# domus-silicea-board01-schematic.net
KiCad netlist of a schematic drawn in EAGLE
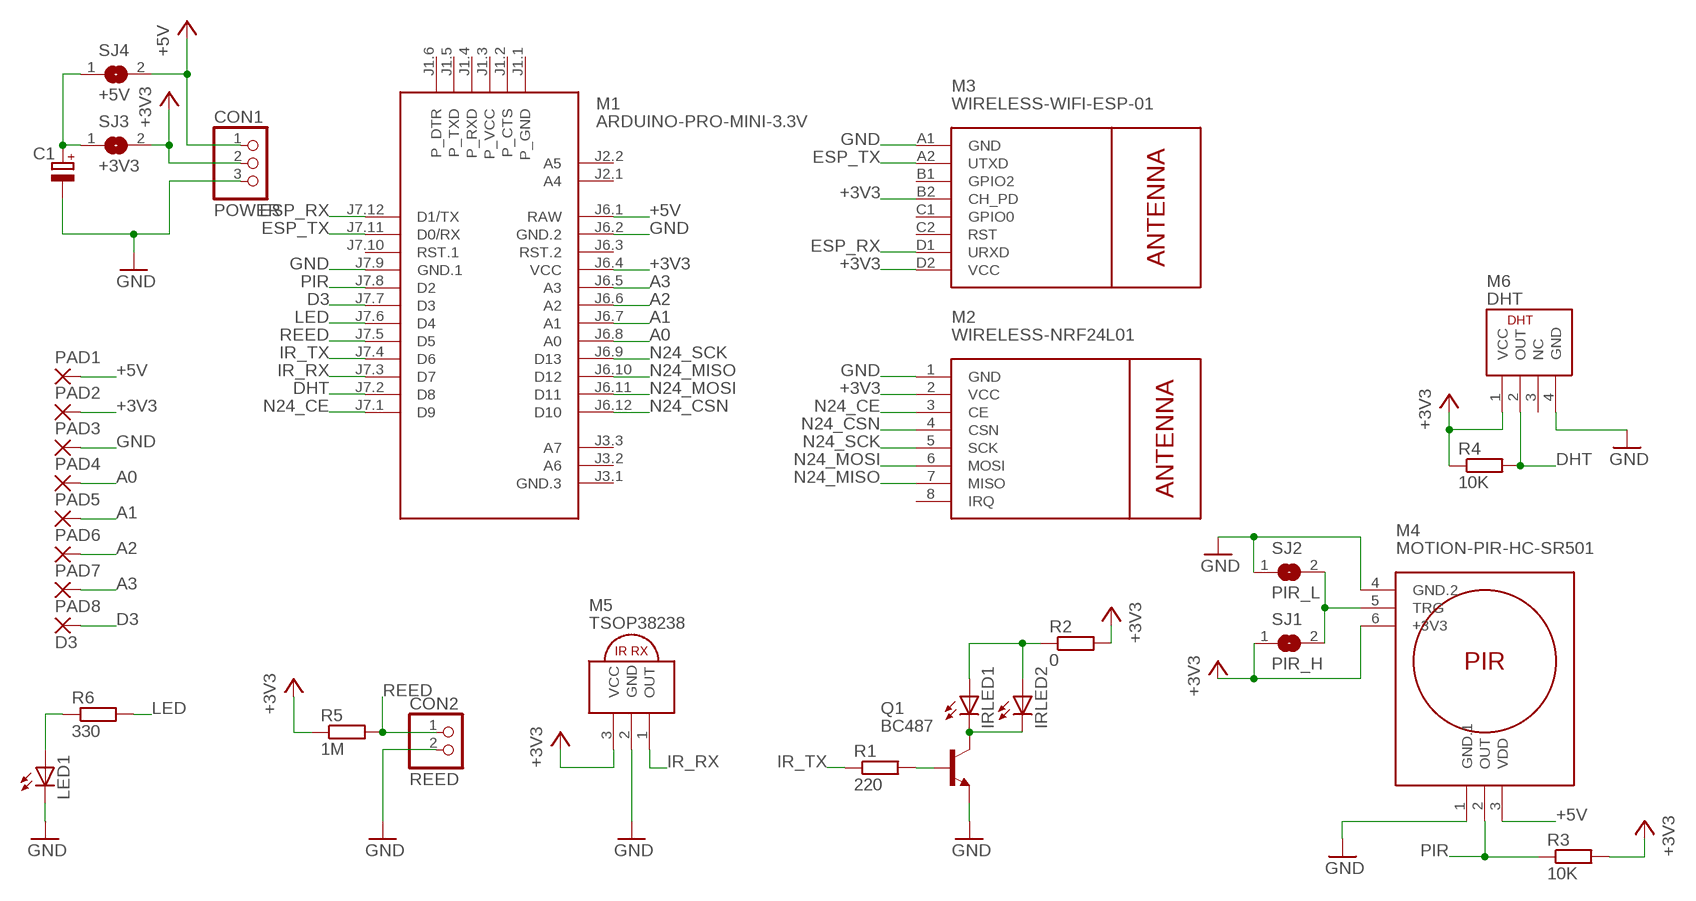
[diagram p0: schematic, sheet 1]

(export (version "E")
  (design (tool "Eeschema 10.0.6"))
  (components
    (comp (ref "C1")
      (value "CPOL-EUE2,5-6E")
      (footprint "eagle-import:E2,5-6E")
      (libsource (lib "eagle-import") (part "CPOL-EUE2,5-6E"))
    )
    (comp (ref "CON1")
      (value "POWER")
      (footprint "eagle-import:1X03")
      (libsource (lib "eagle-import") (part "PINHD-1X3"))
    )
    (comp (ref "CON2")
      (value "REED")
      (footprint "eagle-import:1X02")
      (libsource (lib "eagle-import") (part "PINHD-1X2"))
    )
    (comp (ref "IRLED1")
      (value "LED5MM")
      (footprint "eagle-import:LED5MM")
      (libsource (lib "eagle-import") (part "LED5MM"))
    )
    (comp (ref "IRLED2")
      (value "LED5MM")
      (footprint "eagle-import:LED5MM")
      (libsource (lib "eagle-import") (part "LED5MM"))
    )
    (comp (ref "LED1")
      (value "LED5MM")
      (footprint "eagle-import:LED5MM")
      (libsource (lib "eagle-import") (part "LED5MM"))
    )
    (comp (ref "M1")
      (value "ARDUINO-PRO-MINI-3.3V")
      (footprint "eagle-import:ARDUINO-PRO-MINI")
      (libsource (lib "eagle-import") (part "ARDUINO-PRO-MINI-3.3V"))
    )
    (comp (ref "M2")
      (value "WIRELESS-NRF24L01")
      (footprint "eagle-import:WIRELESS-NRF24L01")
      (libsource (lib "eagle-import") (part "WIRELESS-NRF24L01"))
    )
    (comp (ref "M3")
      (value "WIRELESS-WIFI-ESP-01")
      (footprint "eagle-import:WIRELESS-WIFI-ESP-01")
      (libsource (lib "eagle-import") (part "WIRELESS-WIFI-ESP-01"))
    )
    (comp (ref "M4")
      (value "MOTION-PIR-HC-SR501")
      (footprint "eagle-import:MOTION-PIR-HC-SR501")
      (libsource (lib "eagle-import") (part "MOTION-PIR-HC-SR501"))
    )
    (comp (ref "M5")
      (value "TSOP38238")
      (footprint "eagle-import:TSOP38238")
      (libsource (lib "eagle-import") (part "TSOP38238"))
    )
    (comp (ref "M6")
      (value "DHT")
      (footprint "eagle-import:DHT")
      (libsource (lib "eagle-import") (part "DHT"))
    )
    (comp (ref "PAD1")
      (value "2,54/1,0")
      (footprint "eagle-import:2,54_1,0")
      (libsource (lib "eagle-import") (part "2,54/1,0"))
    )
    (comp (ref "PAD2")
      (value "2,54/1,0")
      (footprint "eagle-import:2,54_1,0")
      (libsource (lib "eagle-import") (part "2,54/1,0"))
    )
    (comp (ref "PAD3")
      (value "2,54/1,0")
      (footprint "eagle-import:2,54_1,0")
      (libsource (lib "eagle-import") (part "2,54/1,0"))
    )
    (comp (ref "PAD4")
      (value "2,54/1,0")
      (footprint "eagle-import:2,54_1,0")
      (libsource (lib "eagle-import") (part "2,54/1,0"))
    )
    (comp (ref "PAD5")
      (value "2,54/1,0")
      (footprint "eagle-import:2,54_1,0")
      (libsource (lib "eagle-import") (part "2,54/1,0"))
    )
    (comp (ref "PAD6")
      (value "2,54/1,0")
      (footprint "eagle-import:2,54_1,0")
      (libsource (lib "eagle-import") (part "2,54/1,0"))
    )
    (comp (ref "PAD7")
      (value "2,54/1,0")
      (footprint "eagle-import:2,54_1,0")
      (libsource (lib "eagle-import") (part "2,54/1,0"))
    )
    (comp (ref "PAD8")
      (value "D3")
      (footprint "eagle-import:2,54_1,0")
      (libsource (lib "eagle-import") (part "2,54/1,0"))
    )
    (comp (ref "Q1")
      (value "BC487")
      (footprint "eagle-import:TO92-EBC")
      (libsource (lib "eagle-import") (part "BC487"))
    )
    (comp (ref "R1")
      (value "220")
      (footprint "eagle-import:0207_10")
      (libsource (lib "eagle-import") (part "R-EU_0207/10"))
    )
    (comp (ref "R2")
      (value "0")
      (footprint "eagle-import:0207_10")
      (libsource (lib "eagle-import") (part "R-EU_0207/10"))
    )
    (comp (ref "R3")
      (value "10K")
      (footprint "eagle-import:0207_10")
      (libsource (lib "eagle-import") (part "R-EU_0207/10"))
    )
    (comp (ref "R4")
      (value "10K")
      (footprint "eagle-import:0207_10")
      (libsource (lib "eagle-import") (part "R-EU_0207/10"))
    )
    (comp (ref "R5")
      (value "1M")
      (footprint "eagle-import:0207_10")
      (libsource (lib "eagle-import") (part "R-EU_0207/10"))
    )
    (comp (ref "R6")
      (value "330")
      (footprint "eagle-import:0207_10")
      (libsource (lib "eagle-import") (part "R-EU_0207/10"))
    )
    (comp (ref "SJ1")
      (value "PIR_H")
      (footprint "eagle-import:SJ")
      (libsource (lib "eagle-import") (part "SJ"))
    )
    (comp (ref "SJ2")
      (value "PIR_L")
      (footprint "eagle-import:SJ")
      (libsource (lib "eagle-import") (part "SJ"))
    )
    (comp (ref "SJ3")
      (value "+3V3")
      (footprint "eagle-import:SJ")
      (libsource (lib "eagle-import") (part "SJ"))
    )
    (comp (ref "SJ4")
      (value "+5V")
      (footprint "eagle-import:SJ")
      (libsource (lib "eagle-import") (part "SJ"))
    )
  )
  (nets
    (net (code "1") (name "+3V3") (class "Default")
      (node (ref "CON1") (pin "2") (pinfunction "2_2") (pintype "passive"))
      (node (ref "M1") (pin "J6.4") (pinfunction "VCC_J6.4") (pintype "power_in"))
      (node (ref "M2") (pin "2") (pinfunction "VCC_2") (pintype "power_in"))
      (node (ref "M3") (pin "B2") (pinfunction "CH_PD_B2") (pintype "bidirectional"))
      (node (ref "M3") (pin "D2") (pinfunction "VCC_D2") (pintype "power_in"))
      (node (ref "M4") (pin "6") (pinfunction "+3V3_6") (pintype "power_in"))
      (node (ref "M5") (pin "3") (pinfunction "VCC_3") (pintype "power_in"))
      (node (ref "M6") (pin "1") (pinfunction "VCC_1") (pintype "power_in"))
      (node (ref "PAD2") (pin "1") (pinfunction "P_1") (pintype "passive"))
      (node (ref "R2") (pin "2") (pinfunction "2_2") (pintype "passive"))
      (node (ref "R3") (pin "2") (pinfunction "2_2") (pintype "passive"))
      (node (ref "R4") (pin "1") (pinfunction "1_1") (pintype "passive"))
      (node (ref "R5") (pin "1") (pinfunction "1_1") (pintype "passive"))
      (node (ref "SJ1") (pin "1") (pinfunction "1_1") (pintype "passive"))
      (node (ref "SJ3") (pin "2") (pinfunction "2_2") (pintype "passive"))
    )
    (net (code "2") (name "+5V") (class "Default")
      (node (ref "CON1") (pin "1") (pinfunction "1_1") (pintype "passive"))
      (node (ref "M1") (pin "J6.1") (pinfunction "RAW_J6.1") (pintype "power_in"))
      (node (ref "M4") (pin "3") (pinfunction "VDD_3") (pintype "power_in"))
      (node (ref "PAD1") (pin "1") (pinfunction "P_1") (pintype "passive"))
      (node (ref "SJ4") (pin "2") (pinfunction "2_2") (pintype "passive"))
    )
    (net (code "3") (name "/A0") (class "Default")
      (node (ref "M1") (pin "J6.8") (pinfunction "A0_J6.8") (pintype "bidirectional"))
      (node (ref "PAD4") (pin "1") (pinfunction "P_1") (pintype "passive"))
    )
    (net (code "4") (name "/A1") (class "Default")
      (node (ref "M1") (pin "J6.7") (pinfunction "A1_J6.7") (pintype "bidirectional"))
      (node (ref "PAD5") (pin "1") (pinfunction "P_1") (pintype "passive"))
    )
    (net (code "5") (name "/A2") (class "Default")
      (node (ref "M1") (pin "J6.6") (pinfunction "A2_J6.6") (pintype "bidirectional"))
      (node (ref "PAD6") (pin "1") (pinfunction "P_1") (pintype "passive"))
    )
    (net (code "6") (name "/A3") (class "Default")
      (node (ref "M1") (pin "J6.5") (pinfunction "A3_J6.5") (pintype "bidirectional"))
      (node (ref "PAD7") (pin "1") (pinfunction "P_1") (pintype "passive"))
    )
    (net (code "7") (name "/D3") (class "Default")
      (node (ref "M1") (pin "J7.7") (pinfunction "D3_J7.7") (pintype "bidirectional"))
      (node (ref "PAD8") (pin "1") (pinfunction "P_1") (pintype "passive"))
    )
    (net (code "8") (name "/DHT") (class "Default")
      (node (ref "M1") (pin "J7.2") (pinfunction "D8_J7.2") (pintype "bidirectional"))
      (node (ref "M6") (pin "2") (pinfunction "OUT_2") (pintype "output"))
      (node (ref "R4") (pin "2") (pinfunction "2_2") (pintype "passive"))
    )
    (net (code "9") (name "/ESP_RX") (class "Default")
      (node (ref "M1") (pin "J7.12") (pinfunction "D1/TX_J7.12") (pintype "bidirectional"))
      (node (ref "M3") (pin "D1") (pinfunction "URXD_D1") (pintype "bidirectional"))
    )
    (net (code "10") (name "/ESP_TX") (class "Default")
      (node (ref "M1") (pin "J7.11") (pinfunction "D0/RX_J7.11") (pintype "bidirectional"))
      (node (ref "M3") (pin "A2") (pinfunction "UTXD_A2") (pintype "bidirectional"))
    )
    (net (code "11") (name "/IR_RX") (class "Default")
      (node (ref "M1") (pin "J7.3") (pinfunction "D7_J7.3") (pintype "bidirectional"))
      (node (ref "M5") (pin "1") (pinfunction "OUT_1") (pintype "output"))
    )
    (net (code "12") (name "/IR_TX") (class "Default")
      (node (ref "M1") (pin "J7.4") (pinfunction "D6_J7.4") (pintype "bidirectional"))
      (node (ref "R1") (pin "1") (pinfunction "1_1") (pintype "passive"))
    )
    (net (code "13") (name "/LED") (class "Default")
      (node (ref "M1") (pin "J7.6") (pinfunction "D4_J7.6") (pintype "bidirectional"))
      (node (ref "R6") (pin "2") (pinfunction "2_2") (pintype "passive"))
    )
    (net (code "14") (name "/N24_CE") (class "Default")
      (node (ref "M1") (pin "J7.1") (pinfunction "D9_J7.1") (pintype "bidirectional"))
      (node (ref "M2") (pin "3") (pinfunction "CE_3") (pintype "bidirectional"))
    )
    (net (code "15") (name "/N24_CSN") (class "Default")
      (node (ref "M1") (pin "J6.12") (pinfunction "D10_J6.12") (pintype "bidirectional"))
      (node (ref "M2") (pin "4") (pinfunction "CSN_4") (pintype "bidirectional"))
    )
    (net (code "16") (name "/N24_MISO") (class "Default")
      (node (ref "M1") (pin "J6.10") (pinfunction "D12_J6.10") (pintype "bidirectional"))
      (node (ref "M2") (pin "7") (pinfunction "MISO_7") (pintype "bidirectional"))
    )
    (net (code "17") (name "/N24_MOSI") (class "Default")
      (node (ref "M1") (pin "J6.11") (pinfunction "D11_J6.11") (pintype "bidirectional"))
      (node (ref "M2") (pin "6") (pinfunction "MOSI_6") (pintype "bidirectional"))
    )
    (net (code "18") (name "/N24_SCK") (class "Default")
      (node (ref "M1") (pin "J6.9") (pinfunction "D13_J6.9") (pintype "bidirectional"))
      (node (ref "M2") (pin "5") (pinfunction "SCK_5") (pintype "bidirectional"))
    )
    (net (code "19") (name "/PIR") (class "Default")
      (node (ref "M1") (pin "J7.8") (pinfunction "D2_J7.8") (pintype "bidirectional"))
      (node (ref "M4") (pin "2") (pinfunction "OUT_2") (pintype "output"))
      (node (ref "R3") (pin "1") (pinfunction "1_1") (pintype "passive"))
    )
    (net (code "20") (name "/REED") (class "Default")
      (node (ref "CON2") (pin "1") (pinfunction "1_1") (pintype "passive"))
      (node (ref "M1") (pin "J7.5") (pinfunction "D5_J7.5") (pintype "bidirectional"))
      (node (ref "R5") (pin "2") (pinfunction "2_2") (pintype "passive"))
    )
    (net (code "21") (name "GND") (class "Default")
      (node (ref "C1") (pin "-") (pinfunction "-_-") (pintype "passive"))
      (node (ref "CON1") (pin "3") (pinfunction "3_3") (pintype "passive"))
      (node (ref "CON2") (pin "2") (pinfunction "2_2") (pintype "passive"))
      (node (ref "LED1") (pin "K") (pinfunction "C_K") (pintype "passive"))
      (node (ref "M1") (pin "J6.2") (pinfunction "GND.2_J6.2") (pintype "power_in"))
      (node (ref "M1") (pin "J7.9") (pinfunction "GND.1_J7.9") (pintype "power_in"))
      (node (ref "M2") (pin "1") (pinfunction "GND_1") (pintype "power_in"))
      (node (ref "M3") (pin "A1") (pinfunction "GND_A1") (pintype "power_in"))
      (node (ref "M4") (pin "1") (pinfunction "GND.1_1") (pintype "power_in"))
      (node (ref "M4") (pin "4") (pinfunction "GND.2_4") (pintype "power_in"))
      (node (ref "M5") (pin "2") (pinfunction "GND_2") (pintype "power_in"))
      (node (ref "M6") (pin "4") (pinfunction "GND_4") (pintype "power_in"))
      (node (ref "PAD3") (pin "1") (pinfunction "P_1") (pintype "passive"))
      (node (ref "Q1") (pin "E") (pinfunction "E_E") (pintype "passive"))
      (node (ref "SJ2") (pin "1") (pinfunction "1_1") (pintype "passive"))
    )
    (net (code "22") (name "Net-(C1-Pad+)") (class "Default")
      (node (ref "C1") (pin "+") (pinfunction "+_+") (pintype "passive"))
      (node (ref "SJ3") (pin "1") (pinfunction "1_1") (pintype "passive"))
      (node (ref "SJ4") (pin "1") (pinfunction "1_1") (pintype "passive"))
    )
    (net (code "23") (name "Net-(IRLED1-C)") (class "Default")
      (node (ref "IRLED1") (pin "K") (pinfunction "C_K") (pintype "passive"))
      (node (ref "IRLED2") (pin "K") (pinfunction "C_K") (pintype "passive"))
      (node (ref "Q1") (pin "C") (pinfunction "C_C") (pintype "passive"))
    )
    (net (code "24") (name "Net-(IRLED1-PadA)") (class "Default")
      (node (ref "IRLED1") (pin "A") (pinfunction "A_A") (pintype "passive"))
      (node (ref "IRLED2") (pin "A") (pinfunction "A_A") (pintype "passive"))
      (node (ref "R2") (pin "1") (pinfunction "1_1") (pintype "passive"))
    )
    (net (code "25") (name "Net-(LED1-PadA)") (class "Default")
      (node (ref "LED1") (pin "A") (pinfunction "A_A") (pintype "passive"))
      (node (ref "R6") (pin "1") (pinfunction "1_1") (pintype "passive"))
    )
    (net (code "26") (name "Net-(M4-TRG)") (class "Default")
      (node (ref "M4") (pin "5") (pinfunction "TRG_5") (pintype "input"))
      (node (ref "SJ1") (pin "2") (pinfunction "2_2") (pintype "passive"))
      (node (ref "SJ2") (pin "2") (pinfunction "2_2") (pintype "passive"))
    )
    (net (code "27") (name "Net-(Q1-PadB)") (class "Default")
      (node (ref "Q1") (pin "B") (pinfunction "B_B") (pintype "passive"))
      (node (ref "R1") (pin "2") (pinfunction "2_2") (pintype "passive"))
    )
    (net (code "28") (name "unconnected-(M1-A4-PadJ2.1)") (class "Default")
      (node (ref "M1") (pin "J2.1") (pinfunction "A4_J2.1") (pintype "bidirectional"))
    )
    (net (code "29") (name "unconnected-(M1-A5-PadJ2.2)") (class "Default")
      (node (ref "M1") (pin "J2.2") (pinfunction "A5_J2.2") (pintype "bidirectional"))
    )
    (net (code "30") (name "unconnected-(M1-A6-PadJ3.2)") (class "Default")
      (node (ref "M1") (pin "J3.2") (pinfunction "A6_J3.2") (pintype "bidirectional"))
    )
    (net (code "31") (name "unconnected-(M1-A7-PadJ3.3)") (class "Default")
      (node (ref "M1") (pin "J3.3") (pinfunction "A7_J3.3") (pintype "bidirectional"))
    )
    (net (code "32") (name "unconnected-(M1-GND.3-PadJ3.1)") (class "Default")
      (node (ref "M1") (pin "J3.1") (pinfunction "GND.3_J3.1") (pintype "bidirectional"))
    )
    (net (code "33") (name "unconnected-(M1-P_CTS-PadJ1.2)") (class "Default")
      (node (ref "M1") (pin "J1.2") (pinfunction "P_CTS_J1.2") (pintype "bidirectional"))
    )
    (net (code "34") (name "unconnected-(M1-P_DTR-PadJ1.6)") (class "Default")
      (node (ref "M1") (pin "J1.6") (pinfunction "P_DTR_J1.6") (pintype "bidirectional"))
    )
    (net (code "35") (name "unconnected-(M1-P_GND-PadJ1.1)") (class "Default")
      (node (ref "M1") (pin "J1.1") (pinfunction "P_GND_J1.1") (pintype "bidirectional"))
    )
    (net (code "36") (name "unconnected-(M1-P_RXD-PadJ1.4)") (class "Default")
      (node (ref "M1") (pin "J1.4") (pinfunction "P_RXD_J1.4") (pintype "bidirectional"))
    )
    (net (code "37") (name "unconnected-(M1-P_TXD-PadJ1.5)") (class "Default")
      (node (ref "M1") (pin "J1.5") (pinfunction "P_TXD_J1.5") (pintype "bidirectional"))
    )
    (net (code "38") (name "unconnected-(M1-P_VCC-PadJ1.3)") (class "Default")
      (node (ref "M1") (pin "J1.3") (pinfunction "P_VCC_J1.3") (pintype "bidirectional"))
    )
    (net (code "39") (name "unconnected-(M1-RST.1-PadJ7.10)") (class "Default")
      (node (ref "M1") (pin "J7.10") (pinfunction "RST.1_J7.10") (pintype "bidirectional"))
    )
    (net (code "40") (name "unconnected-(M1-RST.2-PadJ6.3)") (class "Default")
      (node (ref "M1") (pin "J6.3") (pinfunction "RST.2_J6.3") (pintype "bidirectional"))
    )
    (net (code "41") (name "unconnected-(M2-IRQ-Pad8)") (class "Default")
      (node (ref "M2") (pin "8") (pinfunction "IRQ_8") (pintype "bidirectional"))
    )
    (net (code "42") (name "unconnected-(M3-GPIO0-PadC1)") (class "Default")
      (node (ref "M3") (pin "C1") (pinfunction "GPIO0_C1") (pintype "bidirectional"))
    )
    (net (code "43") (name "unconnected-(M3-GPIO2-PadB1)") (class "Default")
      (node (ref "M3") (pin "B1") (pinfunction "GPIO2_B1") (pintype "bidirectional"))
    )
    (net (code "44") (name "unconnected-(M3-RST-PadC2)") (class "Default")
      (node (ref "M3") (pin "C2") (pinfunction "RST_C2") (pintype "bidirectional"))
    )
    (net (code "45") (name "unconnected-(M6-NC-Pad3)") (class "Default")
      (node (ref "M6") (pin "3") (pinfunction "NC_3") (pintype "output"))
    )
  )
)
